# FPGA_Power.net
KiCad netlist of a schematic drawn in Altium Designer
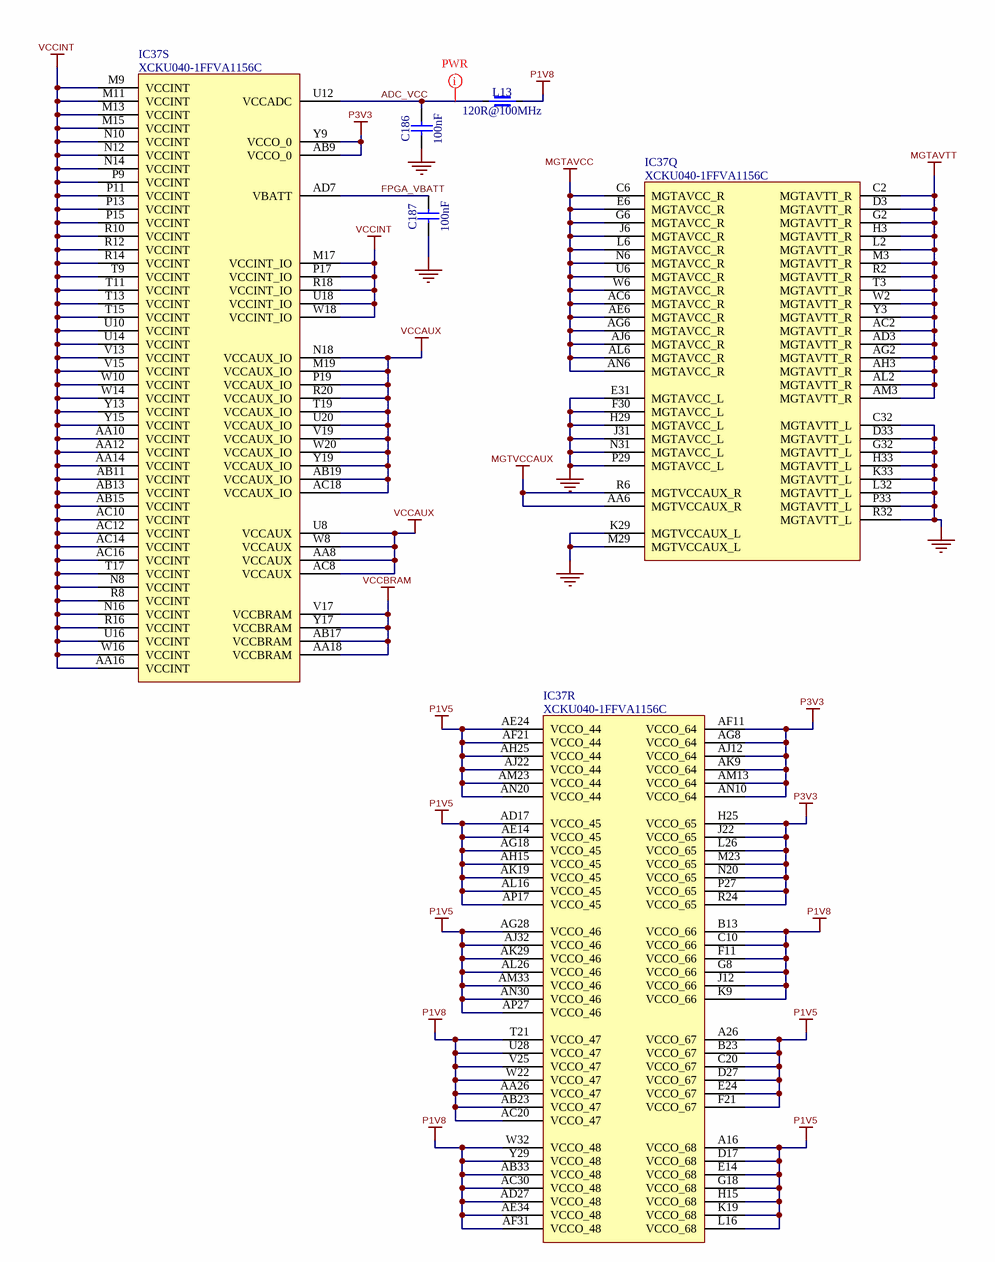
[diagram p0: FPGA_Power.SchDoc]

(export (version "E")
  (design (tool "Eeschema 10.0.6"))
  (components
    (comp (ref "C186")
      (value "100nF")
      (footprint "CAPC0603X33N")
      (description "Non-polarised capacitor")
      (fields
        (field (name "MANUFACTURER PART NUMBER") "CC0201_100NF_6.3V_10%_X5R")
        (field (name "MANUFACTURER") "GENERIC")
        (field (name "AUTHOR") "CERN DEM JLC")
      )
      (libsource (lib "Capacitors") (part "Capacitor - non polarized"))
    )
    (comp (ref "C187")
      (value "100nF")
      (footprint "CAPC0603X33N")
      (description "Non-polarised capacitor")
      (fields
        (field (name "MANUFACTURER PART NUMBER") "CC0201_100NF_6.3V_10%_X5R")
        (field (name "MANUFACTURER") "GENERIC")
        (field (name "AUTHOR") "CERN DEM JLC")
      )
      (libsource (lib "Capacitors") (part "Capacitor - non polarized"))
    )
    (comp (ref "IC37")
      (value "XCKU040-1FFVA1156C")
      (footprint "BGA1156C100P34X34_3500X3500X350")
      (description "Kintex UltraScale FPGA, 520 I/O, 530K Cells, 1156-Ball BGA, Speed Grade 1, Commercial Grade")
      (fields (field (name "MANUFACTURER") "XILINX") (field (name "AUTHOR") "CERN DEM CA"))
      (libsource (lib "ICs And Semiconductors") (part "XCKU040-1FFVA1156C"))
    )
    (comp (ref "L13")
      (value "120R@100MHz")
      (footprint "INDC1005X55N")
      (fields
        (field (name "MANUFACTURER PART NUMBER") "BLM15PX121SN1D")
        (field (name "MANUFACTURER") "MURATA")
        (field (name "PART NUMBER") "IND0402_MURATA_BLM15PX121SN1D")
        (field (name "AUTHOR") "CERN DEM JMW")
      )
      (libsource (lib "Inductors & Transformers") (part "Ferrite Bead"))
    )
  )
  (nets
    (net (code "1") (name "/ADC_VCC") (class "Default")
      (node (ref "C186") (pin "2") (pinfunction "2_2") (pintype "passive"))
      (node (ref "IC37") (pin "U12") (pinfunction "VCCADC_U12") (pintype "power_in"))
      (node (ref "L13") (pin "1") (pinfunction "1_1") (pintype "passive"))
    )
    (net (code "2") (name "/FPGA_VBATT") (class "Default")
      (node (ref "C187") (pin "2") (pinfunction "2_2") (pintype "passive"))
      (node (ref "IC37") (pin "AD7") (pinfunction "VBATT_AD7") (pintype "power_in"))
    )
    (net (code "3") (name "GND") (class "Default")
      (node (ref "C186") (pin "1") (pinfunction "1_1") (pintype "passive"))
      (node (ref "C187") (pin "1") (pinfunction "1_1") (pintype "passive"))
      (node (ref "IC37") (pin "C32") (pinfunction "MGTAVTT_L_C32") (pintype "power_in"))
      (node (ref "IC37") (pin "D33") (pinfunction "MGTAVTT_L_D33") (pintype "power_in"))
      (node (ref "IC37") (pin "E31") (pinfunction "MGTAVCC_L_E31") (pintype "power_in"))
      (node (ref "IC37") (pin "F30") (pinfunction "MGTAVCC_L_F30") (pintype "power_in"))
      (node (ref "IC37") (pin "G32") (pinfunction "MGTAVTT_L_G32") (pintype "power_in"))
      (node (ref "IC37") (pin "H29") (pinfunction "MGTAVCC_L_H29") (pintype "power_in"))
      (node (ref "IC37") (pin "H33") (pinfunction "MGTAVTT_L_H33") (pintype "power_in"))
      (node (ref "IC37") (pin "J31") (pinfunction "MGTAVCC_L_J31") (pintype "power_in"))
      (node (ref "IC37") (pin "K29") (pinfunction "MGTVCCAUX_L_K29") (pintype "power_in"))
      (node (ref "IC37") (pin "K33") (pinfunction "MGTAVTT_L_K33") (pintype "power_in"))
      (node (ref "IC37") (pin "L32") (pinfunction "MGTAVTT_L_L32") (pintype "power_in"))
      (node (ref "IC37") (pin "M29") (pinfunction "MGTVCCAUX_L_M29") (pintype "power_in"))
      (node (ref "IC37") (pin "N31") (pinfunction "MGTAVCC_L_N31") (pintype "power_in"))
      (node (ref "IC37") (pin "P29") (pinfunction "MGTAVCC_L_P29") (pintype "power_in"))
      (node (ref "IC37") (pin "P33") (pinfunction "MGTAVTT_L_P33") (pintype "power_in"))
      (node (ref "IC37") (pin "R32") (pinfunction "MGTAVTT_L_R32") (pintype "power_in"))
    )
    (net (code "4") (name "MGTAVCC") (class "Default")
      (node (ref "IC37") (pin "AC6") (pinfunction "MGTAVCC_R_AC6") (pintype "power_in"))
      (node (ref "IC37") (pin "AE6") (pinfunction "MGTAVCC_R_AE6") (pintype "power_in"))
      (node (ref "IC37") (pin "AG6") (pinfunction "MGTAVCC_R_AG6") (pintype "power_in"))
      (node (ref "IC37") (pin "AJ6") (pinfunction "MGTAVCC_R_AJ6") (pintype "power_in"))
      (node (ref "IC37") (pin "AL6") (pinfunction "MGTAVCC_R_AL6") (pintype "power_in"))
      (node (ref "IC37") (pin "AN6") (pinfunction "MGTAVCC_R_AN6") (pintype "power_in"))
      (node (ref "IC37") (pin "C6") (pinfunction "MGTAVCC_R_C6") (pintype "power_in"))
      (node (ref "IC37") (pin "E6") (pinfunction "MGTAVCC_R_E6") (pintype "power_in"))
      (node (ref "IC37") (pin "G6") (pinfunction "MGTAVCC_R_G6") (pintype "power_in"))
      (node (ref "IC37") (pin "J6") (pinfunction "MGTAVCC_R_J6") (pintype "power_in"))
      (node (ref "IC37") (pin "L6") (pinfunction "MGTAVCC_R_L6") (pintype "power_in"))
      (node (ref "IC37") (pin "N6") (pinfunction "MGTAVCC_R_N6") (pintype "power_in"))
      (node (ref "IC37") (pin "U6") (pinfunction "MGTAVCC_R_U6") (pintype "power_in"))
      (node (ref "IC37") (pin "W6") (pinfunction "MGTAVCC_R_W6") (pintype "power_in"))
    )
    (net (code "5") (name "MGTAVTT") (class "Default")
      (node (ref "IC37") (pin "AC2") (pinfunction "MGTAVTT_R_AC2") (pintype "power_in"))
      (node (ref "IC37") (pin "AD3") (pinfunction "MGTAVTT_R_AD3") (pintype "power_in"))
      (node (ref "IC37") (pin "AG2") (pinfunction "MGTAVTT_R_AG2") (pintype "power_in"))
      (node (ref "IC37") (pin "AH3") (pinfunction "MGTAVTT_R_AH3") (pintype "power_in"))
      (node (ref "IC37") (pin "AL2") (pinfunction "MGTAVTT_R_AL2") (pintype "power_in"))
      (node (ref "IC37") (pin "AM3") (pinfunction "MGTAVTT_R_AM3") (pintype "power_in"))
      (node (ref "IC37") (pin "C2") (pinfunction "MGTAVTT_R_C2") (pintype "power_in"))
      (node (ref "IC37") (pin "D3") (pinfunction "MGTAVTT_R_D3") (pintype "power_in"))
      (node (ref "IC37") (pin "G2") (pinfunction "MGTAVTT_R_G2") (pintype "power_in"))
      (node (ref "IC37") (pin "H3") (pinfunction "MGTAVTT_R_H3") (pintype "power_in"))
      (node (ref "IC37") (pin "L2") (pinfunction "MGTAVTT_R_L2") (pintype "power_in"))
      (node (ref "IC37") (pin "M3") (pinfunction "MGTAVTT_R_M3") (pintype "power_in"))
      (node (ref "IC37") (pin "R2") (pinfunction "MGTAVTT_R_R2") (pintype "power_in"))
      (node (ref "IC37") (pin "T3") (pinfunction "MGTAVTT_R_T3") (pintype "power_in"))
      (node (ref "IC37") (pin "W2") (pinfunction "MGTAVTT_R_W2") (pintype "power_in"))
      (node (ref "IC37") (pin "Y3") (pinfunction "MGTAVTT_R_Y3") (pintype "power_in"))
    )
    (net (code "6") (name "MGTVCCAUX") (class "Default")
      (node (ref "IC37") (pin "AA6") (pinfunction "MGTVCCAUX_R_AA6") (pintype "power_in"))
      (node (ref "IC37") (pin "R6") (pinfunction "MGTVCCAUX_R_R6") (pintype "power_in"))
    )
    (net (code "7") (name "P1V5") (class "Default")
      (node (ref "IC37") (pin "A16") (pinfunction "VCCO_68_A16") (pintype "power_in"))
      (node (ref "IC37") (pin "A26") (pinfunction "VCCO_67_A26") (pintype "power_in"))
      (node (ref "IC37") (pin "AD17") (pinfunction "VCCO_45_AD17") (pintype "power_in"))
      (node (ref "IC37") (pin "AE14") (pinfunction "VCCO_45_AE14") (pintype "power_in"))
      (node (ref "IC37") (pin "AE24") (pinfunction "VCCO_44_AE24") (pintype "power_in"))
      (node (ref "IC37") (pin "AF21") (pinfunction "VCCO_44_AF21") (pintype "power_in"))
      (node (ref "IC37") (pin "AG18") (pinfunction "VCCO_45_AG18") (pintype "power_in"))
      (node (ref "IC37") (pin "AG28") (pinfunction "VCCO_46_AG28") (pintype "power_in"))
      (node (ref "IC37") (pin "AH15") (pinfunction "VCCO_45_AH15") (pintype "power_in"))
      (node (ref "IC37") (pin "AH25") (pinfunction "VCCO_44_AH25") (pintype "power_in"))
      (node (ref "IC37") (pin "AJ22") (pinfunction "VCCO_44_AJ22") (pintype "power_in"))
      (node (ref "IC37") (pin "AJ32") (pinfunction "VCCO_46_AJ32") (pintype "power_in"))
      (node (ref "IC37") (pin "AK19") (pinfunction "VCCO_45_AK19") (pintype "power_in"))
      (node (ref "IC37") (pin "AK29") (pinfunction "VCCO_46_AK29") (pintype "power_in"))
      (node (ref "IC37") (pin "AL16") (pinfunction "VCCO_45_AL16") (pintype "power_in"))
      (node (ref "IC37") (pin "AL26") (pinfunction "VCCO_46_AL26") (pintype "power_in"))
      (node (ref "IC37") (pin "AM23") (pinfunction "VCCO_44_AM23") (pintype "power_in"))
      (node (ref "IC37") (pin "AM33") (pinfunction "VCCO_46_AM33") (pintype "power_in"))
      (node (ref "IC37") (pin "AN20") (pinfunction "VCCO_44_AN20") (pintype "power_in"))
      (node (ref "IC37") (pin "AN30") (pinfunction "VCCO_46_AN30") (pintype "power_in"))
      (node (ref "IC37") (pin "AP17") (pinfunction "VCCO_45_AP17") (pintype "power_in"))
      (node (ref "IC37") (pin "AP27") (pinfunction "VCCO_46_AP27") (pintype "power_in"))
      (node (ref "IC37") (pin "B23") (pinfunction "VCCO_67_B23") (pintype "power_in"))
      (node (ref "IC37") (pin "C20") (pinfunction "VCCO_67_C20") (pintype "power_in"))
      (node (ref "IC37") (pin "D17") (pinfunction "VCCO_68_D17") (pintype "power_in"))
      (node (ref "IC37") (pin "D27") (pinfunction "VCCO_67_D27") (pintype "power_in"))
      (node (ref "IC37") (pin "E14") (pinfunction "VCCO_68_E14") (pintype "power_in"))
      (node (ref "IC37") (pin "E24") (pinfunction "VCCO_67_E24") (pintype "power_in"))
      (node (ref "IC37") (pin "F21") (pinfunction "VCCO_67_F21") (pintype "power_in"))
      (node (ref "IC37") (pin "G18") (pinfunction "VCCO_68_G18") (pintype "power_in"))
      (node (ref "IC37") (pin "H15") (pinfunction "VCCO_68_H15") (pintype "power_in"))
      (node (ref "IC37") (pin "K19") (pinfunction "VCCO_68_K19") (pintype "power_in"))
      (node (ref "IC37") (pin "L16") (pinfunction "VCCO_68_L16") (pintype "power_in"))
    )
    (net (code "8") (name "P1V8") (class "Default")
      (node (ref "IC37") (pin "AA26") (pinfunction "VCCO_47_AA26") (pintype "power_in"))
      (node (ref "IC37") (pin "AB23") (pinfunction "VCCO_47_AB23") (pintype "power_in"))
      (node (ref "IC37") (pin "AB33") (pinfunction "VCCO_48_AB33") (pintype "power_in"))
      (node (ref "IC37") (pin "AC20") (pinfunction "VCCO_47_AC20") (pintype "power_in"))
      (node (ref "IC37") (pin "AC30") (pinfunction "VCCO_48_AC30") (pintype "power_in"))
      (node (ref "IC37") (pin "AD27") (pinfunction "VCCO_48_AD27") (pintype "power_in"))
      (node (ref "IC37") (pin "AE34") (pinfunction "VCCO_48_AE34") (pintype "power_in"))
      (node (ref "IC37") (pin "AF31") (pinfunction "VCCO_48_AF31") (pintype "power_in"))
      (node (ref "IC37") (pin "B13") (pinfunction "VCCO_66_B13") (pintype "power_in"))
      (node (ref "IC37") (pin "C10") (pinfunction "VCCO_66_C10") (pintype "power_in"))
      (node (ref "IC37") (pin "F11") (pinfunction "VCCO_66_F11") (pintype "power_in"))
      (node (ref "IC37") (pin "G8") (pinfunction "VCCO_66_G8") (pintype "power_in"))
      (node (ref "IC37") (pin "J12") (pinfunction "VCCO_66_J12") (pintype "power_in"))
      (node (ref "IC37") (pin "K9") (pinfunction "VCCO_66_K9") (pintype "power_in"))
      (node (ref "IC37") (pin "T21") (pinfunction "VCCO_47_T21") (pintype "power_in"))
      (node (ref "IC37") (pin "U28") (pinfunction "VCCO_47_U28") (pintype "power_in"))
      (node (ref "IC37") (pin "V25") (pinfunction "VCCO_47_V25") (pintype "power_in"))
      (node (ref "IC37") (pin "W22") (pinfunction "VCCO_47_W22") (pintype "power_in"))
      (node (ref "IC37") (pin "W32") (pinfunction "VCCO_48_W32") (pintype "power_in"))
      (node (ref "IC37") (pin "Y29") (pinfunction "VCCO_48_Y29") (pintype "power_in"))
      (node (ref "L13") (pin "2") (pinfunction "2_2") (pintype "passive"))
    )
    (net (code "9") (name "P3V3") (class "Default")
      (node (ref "IC37") (pin "AB9") (pinfunction "VCCO_0_AB9") (pintype "power_in"))
      (node (ref "IC37") (pin "AF11") (pinfunction "VCCO_64_AF11") (pintype "power_in"))
      (node (ref "IC37") (pin "AG8") (pinfunction "VCCO_64_AG8") (pintype "power_in"))
      (node (ref "IC37") (pin "AJ12") (pinfunction "VCCO_64_AJ12") (pintype "power_in"))
      (node (ref "IC37") (pin "AK9") (pinfunction "VCCO_64_AK9") (pintype "power_in"))
      (node (ref "IC37") (pin "AM13") (pinfunction "VCCO_64_AM13") (pintype "power_in"))
      (node (ref "IC37") (pin "AN10") (pinfunction "VCCO_64_AN10") (pintype "power_in"))
      (node (ref "IC37") (pin "H25") (pinfunction "VCCO_65_H25") (pintype "power_in"))
      (node (ref "IC37") (pin "J22") (pinfunction "VCCO_65_J22") (pintype "power_in"))
      (node (ref "IC37") (pin "L26") (pinfunction "VCCO_65_L26") (pintype "power_in"))
      (node (ref "IC37") (pin "M23") (pinfunction "VCCO_65_M23") (pintype "power_in"))
      (node (ref "IC37") (pin "N20") (pinfunction "VCCO_65_N20") (pintype "power_in"))
      (node (ref "IC37") (pin "P27") (pinfunction "VCCO_65_P27") (pintype "power_in"))
      (node (ref "IC37") (pin "R24") (pinfunction "VCCO_65_R24") (pintype "power_in"))
      (node (ref "IC37") (pin "Y9") (pinfunction "VCCO_0_Y9") (pintype "power_in"))
    )
    (net (code "10") (name "VCCAUX") (class "Default")
      (node (ref "IC37") (pin "AA8") (pinfunction "VCCAUX_AA8") (pintype "power_in"))
      (node (ref "IC37") (pin "AB19") (pinfunction "VCCAUX_IO_AB19") (pintype "power_in"))
      (node (ref "IC37") (pin "AC18") (pinfunction "VCCAUX_IO_AC18") (pintype "power_in"))
      (node (ref "IC37") (pin "AC8") (pinfunction "VCCAUX_AC8") (pintype "power_in"))
      (node (ref "IC37") (pin "M19") (pinfunction "VCCAUX_IO_M19") (pintype "power_in"))
      (node (ref "IC37") (pin "N18") (pinfunction "VCCAUX_IO_N18") (pintype "power_in"))
      (node (ref "IC37") (pin "P19") (pinfunction "VCCAUX_IO_P19") (pintype "power_in"))
      (node (ref "IC37") (pin "R20") (pinfunction "VCCAUX_IO_R20") (pintype "power_in"))
      (node (ref "IC37") (pin "T19") (pinfunction "VCCAUX_IO_T19") (pintype "power_in"))
      (node (ref "IC37") (pin "U20") (pinfunction "VCCAUX_IO_U20") (pintype "power_in"))
      (node (ref "IC37") (pin "U8") (pinfunction "VCCAUX_U8") (pintype "power_in"))
      (node (ref "IC37") (pin "V19") (pinfunction "VCCAUX_IO_V19") (pintype "power_in"))
      (node (ref "IC37") (pin "W20") (pinfunction "VCCAUX_IO_W20") (pintype "power_in"))
      (node (ref "IC37") (pin "W8") (pinfunction "VCCAUX_W8") (pintype "power_in"))
      (node (ref "IC37") (pin "Y19") (pinfunction "VCCAUX_IO_Y19") (pintype "power_in"))
    )
    (net (code "11") (name "VCCBRAM") (class "Default")
      (node (ref "IC37") (pin "AA18") (pinfunction "VCCBRAM_AA18") (pintype "power_in"))
      (node (ref "IC37") (pin "AB17") (pinfunction "VCCBRAM_AB17") (pintype "power_in"))
      (node (ref "IC37") (pin "V17") (pinfunction "VCCBRAM_V17") (pintype "power_in"))
      (node (ref "IC37") (pin "Y17") (pinfunction "VCCBRAM_Y17") (pintype "power_in"))
    )
    (net (code "12") (name "VCCINT") (class "Default")
      (node (ref "IC37") (pin "AA10") (pinfunction "VCCINT_AA10") (pintype "power_in"))
      (node (ref "IC37") (pin "AA12") (pinfunction "VCCINT_AA12") (pintype "power_in"))
      (node (ref "IC37") (pin "AA14") (pinfunction "VCCINT_AA14") (pintype "power_in"))
      (node (ref "IC37") (pin "AA16") (pinfunction "VCCINT_AA16") (pintype "power_in"))
      (node (ref "IC37") (pin "AB11") (pinfunction "VCCINT_AB11") (pintype "power_in"))
      (node (ref "IC37") (pin "AB13") (pinfunction "VCCINT_AB13") (pintype "power_in"))
      (node (ref "IC37") (pin "AB15") (pinfunction "VCCINT_AB15") (pintype "power_in"))
      (node (ref "IC37") (pin "AC10") (pinfunction "VCCINT_AC10") (pintype "power_in"))
      (node (ref "IC37") (pin "AC12") (pinfunction "VCCINT_AC12") (pintype "power_in"))
      (node (ref "IC37") (pin "AC14") (pinfunction "VCCINT_AC14") (pintype "power_in"))
      (node (ref "IC37") (pin "AC16") (pinfunction "VCCINT_AC16") (pintype "power_in"))
      (node (ref "IC37") (pin "M11") (pinfunction "VCCINT_M11") (pintype "power_in"))
      (node (ref "IC37") (pin "M13") (pinfunction "VCCINT_M13") (pintype "power_in"))
      (node (ref "IC37") (pin "M15") (pinfunction "VCCINT_M15") (pintype "power_in"))
      (node (ref "IC37") (pin "M17") (pinfunction "VCCINT_IO_M17") (pintype "power_in"))
      (node (ref "IC37") (pin "M9") (pinfunction "VCCINT_M9") (pintype "power_in"))
      (node (ref "IC37") (pin "N10") (pinfunction "VCCINT_N10") (pintype "power_in"))
      (node (ref "IC37") (pin "N12") (pinfunction "VCCINT_N12") (pintype "power_in"))
      (node (ref "IC37") (pin "N14") (pinfunction "VCCINT_N14") (pintype "power_in"))
      (node (ref "IC37") (pin "N16") (pinfunction "VCCINT_N16") (pintype "power_in"))
      (node (ref "IC37") (pin "N8") (pinfunction "VCCINT_N8") (pintype "power_in"))
      (node (ref "IC37") (pin "P11") (pinfunction "VCCINT_P11") (pintype "power_in"))
      (node (ref "IC37") (pin "P13") (pinfunction "VCCINT_P13") (pintype "power_in"))
      (node (ref "IC37") (pin "P15") (pinfunction "VCCINT_P15") (pintype "power_in"))
      (node (ref "IC37") (pin "P17") (pinfunction "VCCINT_IO_P17") (pintype "power_in"))
      (node (ref "IC37") (pin "P9") (pinfunction "VCCINT_P9") (pintype "power_in"))
      (node (ref "IC37") (pin "R10") (pinfunction "VCCINT_R10") (pintype "power_in"))
      (node (ref "IC37") (pin "R12") (pinfunction "VCCINT_R12") (pintype "power_in"))
      (node (ref "IC37") (pin "R14") (pinfunction "VCCINT_R14") (pintype "power_in"))
      (node (ref "IC37") (pin "R16") (pinfunction "VCCINT_R16") (pintype "power_in"))
      (node (ref "IC37") (pin "R18") (pinfunction "VCCINT_IO_R18") (pintype "power_in"))
      (node (ref "IC37") (pin "R8") (pinfunction "VCCINT_R8") (pintype "power_in"))
      (node (ref "IC37") (pin "T11") (pinfunction "VCCINT_T11") (pintype "power_in"))
      (node (ref "IC37") (pin "T13") (pinfunction "VCCINT_T13") (pintype "power_in"))
      (node (ref "IC37") (pin "T15") (pinfunction "VCCINT_T15") (pintype "power_in"))
      (node (ref "IC37") (pin "T17") (pinfunction "VCCINT_T17") (pintype "power_in"))
      (node (ref "IC37") (pin "T9") (pinfunction "VCCINT_T9") (pintype "power_in"))
      (node (ref "IC37") (pin "U10") (pinfunction "VCCINT_U10") (pintype "power_in"))
      (node (ref "IC37") (pin "U14") (pinfunction "VCCINT_U14") (pintype "power_in"))
      (node (ref "IC37") (pin "U16") (pinfunction "VCCINT_U16") (pintype "power_in"))
      (node (ref "IC37") (pin "U18") (pinfunction "VCCINT_IO_U18") (pintype "power_in"))
      (node (ref "IC37") (pin "V13") (pinfunction "VCCINT_V13") (pintype "power_in"))
      (node (ref "IC37") (pin "V15") (pinfunction "VCCINT_V15") (pintype "power_in"))
      (node (ref "IC37") (pin "W10") (pinfunction "VCCINT_W10") (pintype "power_in"))
      (node (ref "IC37") (pin "W14") (pinfunction "VCCINT_W14") (pintype "power_in"))
      (node (ref "IC37") (pin "W16") (pinfunction "VCCINT_W16") (pintype "power_in"))
      (node (ref "IC37") (pin "W18") (pinfunction "VCCINT_IO_W18") (pintype "power_in"))
      (node (ref "IC37") (pin "Y13") (pinfunction "VCCINT_Y13") (pintype "power_in"))
      (node (ref "IC37") (pin "Y15") (pinfunction "VCCINT_Y15") (pintype "power_in"))
    )
  )
)
